# A3901.net
KiCad netlist of a schematic drawn in EAGLE
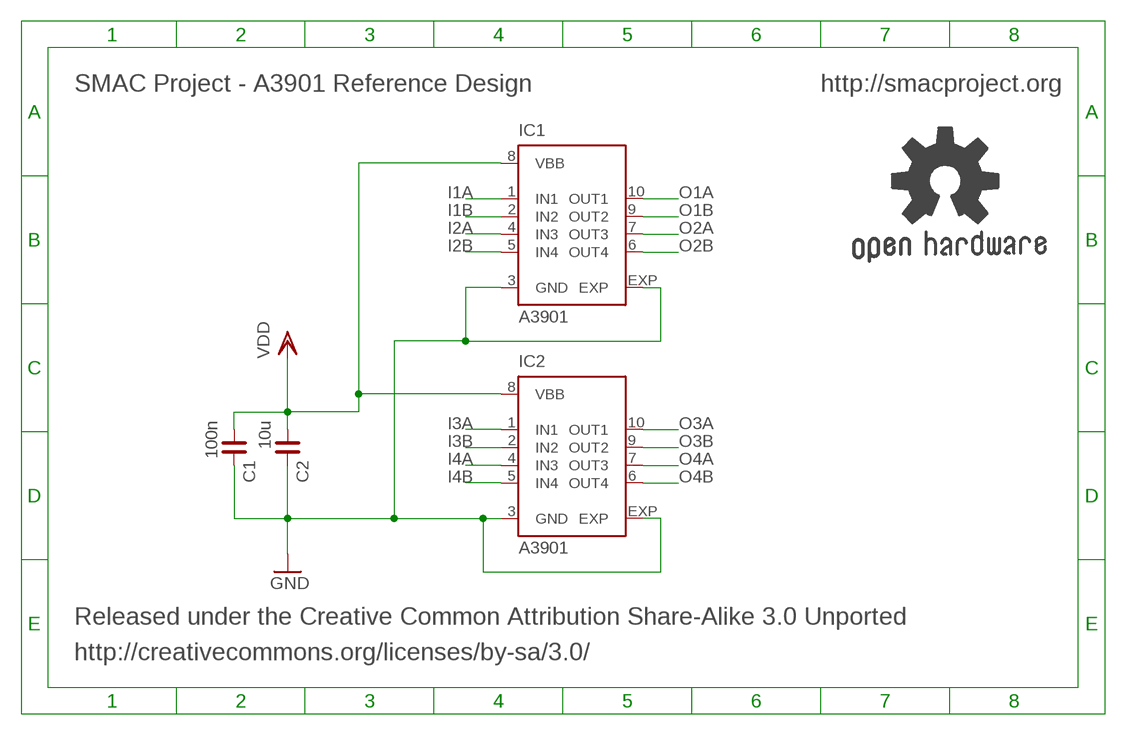
[diagram p0: schematic, sheet 1]

(export (version "E")
  (design (tool "Eeschema 10.0.6"))
  (components
    (comp (ref "C1")
      (value "100n")
      (footprint "eagle-import:C0402")
      (libsource (lib "eagle-import") (part "C_0402"))
    )
    (comp (ref "C2")
      (value "10u")
      (footprint "eagle-import:C0402")
      (libsource (lib "eagle-import") (part "C_0402"))
    )
    (comp (ref "GOLD_ORB_SM1")
      (value "OSHWLOGO_REF_SM")
      (footprint "eagle-import:OSHW2REF")
      (libsource (lib "eagle-import") (part "OSHWLOGO_REF_SM"))
    )
    (comp (ref "IC1")
      (value "A3901")
      (footprint "eagle-import:DFN10-3X3")
      (fields (field (name "MPN") "A3901SEJTR-T"))
      (libsource (lib "eagle-import") (part "A3901"))
    )
    (comp (ref "IC2")
      (value "A3901")
      (footprint "eagle-import:DFN10-3X3")
      (fields (field (name "MPN") "A3901SEJTR-T"))
      (libsource (lib "eagle-import") (part "A3901"))
    )
  )
  (nets
    (net (code "1") (name "/I1A") (class "Default")
      (node (ref "IC1") (pin "1") (pinfunction "IN1_1") (pintype "input"))
    )
    (net (code "2") (name "/I1B") (class "Default")
      (node (ref "IC1") (pin "2") (pinfunction "IN2_2") (pintype "input"))
    )
    (net (code "3") (name "/I2A") (class "Default")
      (node (ref "IC1") (pin "4") (pinfunction "IN3_4") (pintype "input"))
    )
    (net (code "4") (name "/I2B") (class "Default")
      (node (ref "IC1") (pin "5") (pinfunction "IN4_5") (pintype "input"))
    )
    (net (code "5") (name "/I3A") (class "Default")
      (node (ref "IC2") (pin "1") (pinfunction "IN1_1") (pintype "input"))
    )
    (net (code "6") (name "/I3B") (class "Default")
      (node (ref "IC2") (pin "2") (pinfunction "IN2_2") (pintype "input"))
    )
    (net (code "7") (name "/I4A") (class "Default")
      (node (ref "IC2") (pin "4") (pinfunction "IN3_4") (pintype "input"))
    )
    (net (code "8") (name "/I4B") (class "Default")
      (node (ref "IC2") (pin "5") (pinfunction "IN4_5") (pintype "input"))
    )
    (net (code "9") (name "/O1A") (class "Default")
      (node (ref "IC1") (pin "10") (pinfunction "OUT1_10") (pintype "output"))
    )
    (net (code "10") (name "/O1B") (class "Default")
      (node (ref "IC1") (pin "9") (pinfunction "OUT2_9") (pintype "output"))
    )
    (net (code "11") (name "/O2A") (class "Default")
      (node (ref "IC1") (pin "7") (pinfunction "OUT3_7") (pintype "output"))
    )
    (net (code "12") (name "/O2B") (class "Default")
      (node (ref "IC1") (pin "6") (pinfunction "OUT4_6") (pintype "output"))
    )
    (net (code "13") (name "/O3A") (class "Default")
      (node (ref "IC2") (pin "10") (pinfunction "OUT1_10") (pintype "output"))
    )
    (net (code "14") (name "/O3B") (class "Default")
      (node (ref "IC2") (pin "9") (pinfunction "OUT2_9") (pintype "output"))
    )
    (net (code "15") (name "/O4A") (class "Default")
      (node (ref "IC2") (pin "7") (pinfunction "OUT3_7") (pintype "output"))
    )
    (net (code "16") (name "/O4B") (class "Default")
      (node (ref "IC2") (pin "6") (pinfunction "OUT4_6") (pintype "output"))
    )
    (net (code "17") (name "GND") (class "Default")
      (node (ref "C1") (pin "2") (pinfunction "2_2") (pintype "passive"))
      (node (ref "C2") (pin "2") (pinfunction "2_2") (pintype "passive"))
      (node (ref "IC1") (pin "3") (pinfunction "GND_3") (pintype "power_in"))
      (node (ref "IC1") (pin "EXP") (pinfunction "EXP_EXP") (pintype "passive"))
      (node (ref "IC2") (pin "3") (pinfunction "GND_3") (pintype "power_in"))
      (node (ref "IC2") (pin "EXP") (pinfunction "EXP_EXP") (pintype "passive"))
    )
    (net (code "18") (name "VDD") (class "Default")
      (node (ref "C1") (pin "1") (pinfunction "1_1") (pintype "passive"))
      (node (ref "C2") (pin "1") (pinfunction "1_1") (pintype "passive"))
      (node (ref "IC1") (pin "8") (pinfunction "VBB_8") (pintype "power_in"))
      (node (ref "IC2") (pin "8") (pinfunction "VBB_8") (pintype "power_in"))
    )
  )
)
